# arduino.net
KiCad netlist of a schematic drawn in EAGLE
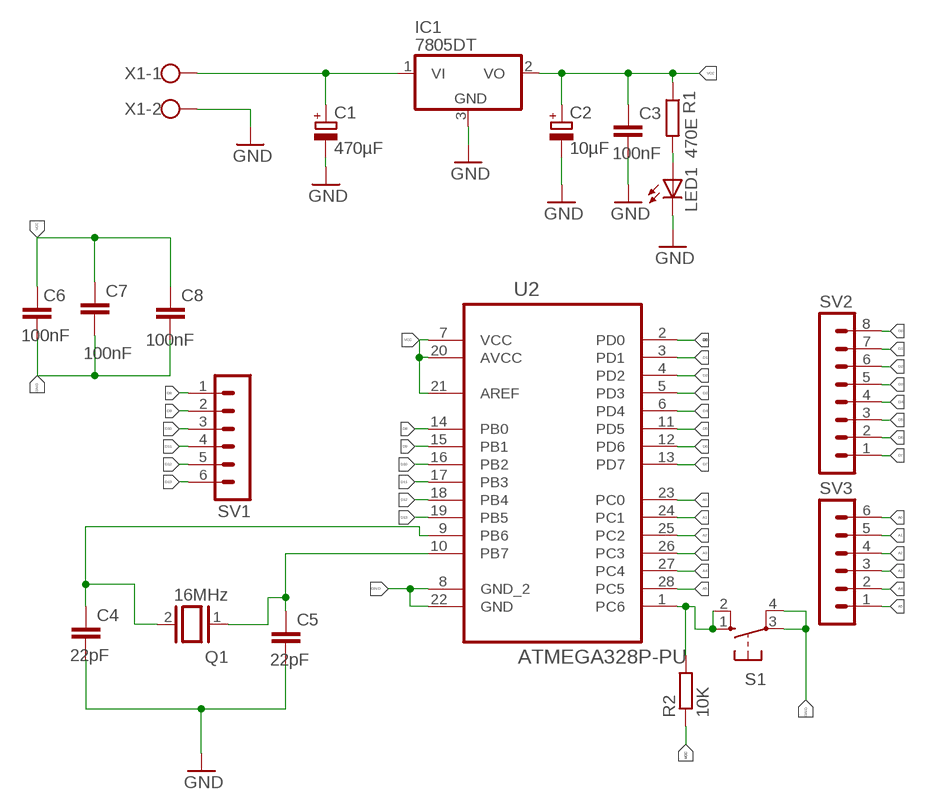
[diagram p0: schematic, sheet 1]

(export (version "E")
  (design (tool "Eeschema 10.0.6"))
  (components
    (comp (ref "C1")
      (value "470µF")
      (footprint "eagle-import:150CLZ-1010")
      (libsource (lib "eagle-import") (part "CPOL-EU150CLZ-1010"))
    )
    (comp (ref "C2")
      (value "10µF")
      (footprint "eagle-import:150CLZ-1010")
      (libsource (lib "eagle-import") (part "CPOL-EU150CLZ-1010"))
    )
    (comp (ref "C3")
      (value "100nF")
      (footprint "eagle-import:C1206")
      (libsource (lib "eagle-import") (part "C-EUC1206"))
    )
    (comp (ref "C4")
      (value "22pF")
      (footprint "eagle-import:C1206")
      (libsource (lib "eagle-import") (part "C-EUC1206"))
    )
    (comp (ref "C5")
      (value "22pF")
      (footprint "eagle-import:C1206")
      (libsource (lib "eagle-import") (part "C-EUC1206"))
    )
    (comp (ref "C6")
      (value "100nF")
      (footprint "eagle-import:C1206")
      (libsource (lib "eagle-import") (part "C-EUC1206"))
    )
    (comp (ref "C7")
      (value "100nF")
      (footprint "eagle-import:C1206")
      (libsource (lib "eagle-import") (part "C-EUC1206"))
    )
    (comp (ref "C8")
      (value "100nF")
      (footprint "eagle-import:C1206")
      (libsource (lib "eagle-import") (part "C-EUC1206"))
    )
    (comp (ref "IC1")
      (value "7805DT")
      (footprint "eagle-import:TO252")
      (libsource (lib "eagle-import") (part "78DT05"))
    )
    (comp (ref "LED1")
      (value "LEDSMT1206")
      (footprint "eagle-import:1206")
      (libsource (lib "eagle-import") (part "LEDSMT1206"))
    )
    (comp (ref "Q1")
      (value "16MHz")
      (footprint "eagle-import:QS")
      (libsource (lib "eagle-import") (part "XTAL/S"))
    )
    (comp (ref "R1")
      (value "470E")
      (footprint "eagle-import:M1206")
      (libsource (lib "eagle-import") (part "resistor_R-EU_M1206"))
    )
    (comp (ref "R2")
      (value "10K")
      (footprint "eagle-import:R1206")
      (libsource (lib "eagle-import") (part "R-EU_R1206"))
    )
    (comp (ref "S1")
      (value "10-XX")
      (footprint "eagle-import:B3F-10XX")
      (fields (field (name "MPN") "B3F-1000"))
      (libsource (lib "eagle-import") (part "10-XX"))
    )
    (comp (ref "SV1")
      (value "MA06-1")
      (footprint "eagle-import:MA06-1")
      (libsource (lib "eagle-import") (part "MA06-1"))
    )
    (comp (ref "SV2")
      (value "MA08-1")
      (footprint "eagle-import:MA08-1")
      (libsource (lib "eagle-import") (part "MA08-1"))
    )
    (comp (ref "SV3")
      (value "MA06-1")
      (footprint "eagle-import:MA06-1")
      (libsource (lib "eagle-import") (part "MA06-1"))
    )
    (comp (ref "U2")
      (value "ATMEGA328P-PU")
      (footprint "eagle-import:DIP254P762X457-28")
      (fields (field (name "MF") "Microchip"))
      (libsource (lib "eagle-import") (part "ATMEGA328P-PU"))
    )
    (comp (ref "X1")
      (value "W237-102")
      (footprint "eagle-import:W237-102")
      (fields (field (name "MPN") "237-102"))
      (libsource (lib "eagle-import") (part "W237-102"))
    )
  )
  (nets
    (net (code "1") (name "A0") (class "Default")
      (node (ref "SV3") (pin "6") (pinfunction "6_6") (pintype "passive"))
      (node (ref "U2") (pin "23") (pinfunction "PC0_23") (pintype "bidirectional"))
    )
    (net (code "2") (name "A1") (class "Default")
      (node (ref "SV3") (pin "5") (pinfunction "5_5") (pintype "passive"))
      (node (ref "U2") (pin "24") (pinfunction "PC1_24") (pintype "bidirectional"))
    )
    (net (code "3") (name "A2") (class "Default")
      (node (ref "SV3") (pin "4") (pinfunction "4_4") (pintype "passive"))
      (node (ref "U2") (pin "25") (pinfunction "PC2_25") (pintype "bidirectional"))
    )
    (net (code "4") (name "A3") (class "Default")
      (node (ref "SV3") (pin "3") (pinfunction "3_3") (pintype "passive"))
      (node (ref "U2") (pin "26") (pinfunction "PC3_26") (pintype "bidirectional"))
    )
    (net (code "5") (name "A4") (class "Default")
      (node (ref "SV3") (pin "2") (pinfunction "2_2") (pintype "passive"))
      (node (ref "U2") (pin "27") (pinfunction "PC4_27") (pintype "bidirectional"))
    )
    (net (code "6") (name "A5") (class "Default")
      (node (ref "SV3") (pin "1") (pinfunction "1_1") (pintype "passive"))
      (node (ref "U2") (pin "28") (pinfunction "PC5_28") (pintype "bidirectional"))
    )
    (net (code "7") (name "D0") (class "Default")
      (node (ref "SV2") (pin "8") (pinfunction "8_8") (pintype "passive"))
      (node (ref "U2") (pin "2") (pinfunction "PD0_2") (pintype "bidirectional"))
    )
    (net (code "8") (name "D1") (class "Default")
      (node (ref "SV2") (pin "7") (pinfunction "7_7") (pintype "passive"))
      (node (ref "U2") (pin "3") (pinfunction "PD1_3") (pintype "bidirectional"))
    )
    (net (code "9") (name "D2") (class "Default")
      (node (ref "SV2") (pin "6") (pinfunction "6_6") (pintype "passive"))
      (node (ref "U2") (pin "4") (pinfunction "PD2_4") (pintype "bidirectional"))
    )
    (net (code "10") (name "D3") (class "Default")
      (node (ref "SV2") (pin "5") (pinfunction "5_5") (pintype "passive"))
      (node (ref "U2") (pin "5") (pinfunction "PD3_5") (pintype "bidirectional"))
    )
    (net (code "11") (name "D4") (class "Default")
      (node (ref "SV2") (pin "4") (pinfunction "4_4") (pintype "passive"))
      (node (ref "U2") (pin "6") (pinfunction "PD4_6") (pintype "bidirectional"))
    )
    (net (code "12") (name "D5") (class "Default")
      (node (ref "SV2") (pin "3") (pinfunction "3_3") (pintype "passive"))
      (node (ref "U2") (pin "11") (pinfunction "PD5_11") (pintype "bidirectional"))
    )
    (net (code "13") (name "D6") (class "Default")
      (node (ref "SV2") (pin "2") (pinfunction "2_2") (pintype "passive"))
      (node (ref "U2") (pin "12") (pinfunction "PD6_12") (pintype "bidirectional"))
    )
    (net (code "14") (name "D7") (class "Default")
      (node (ref "SV2") (pin "1") (pinfunction "1_1") (pintype "passive"))
      (node (ref "U2") (pin "13") (pinfunction "PD7_13") (pintype "bidirectional"))
    )
    (net (code "15") (name "D8") (class "Default")
      (node (ref "SV1") (pin "1") (pinfunction "1_1") (pintype "passive"))
      (node (ref "U2") (pin "14") (pinfunction "PB0_14") (pintype "bidirectional"))
    )
    (net (code "16") (name "D9") (class "Default")
      (node (ref "SV1") (pin "2") (pinfunction "2_2") (pintype "passive"))
      (node (ref "U2") (pin "15") (pinfunction "PB1_15") (pintype "bidirectional"))
    )
    (net (code "17") (name "D10") (class "Default")
      (node (ref "SV1") (pin "3") (pinfunction "3_3") (pintype "passive"))
      (node (ref "U2") (pin "16") (pinfunction "PB2_16") (pintype "bidirectional"))
    )
    (net (code "18") (name "D11") (class "Default")
      (node (ref "SV1") (pin "4") (pinfunction "4_4") (pintype "passive"))
      (node (ref "U2") (pin "17") (pinfunction "PB3_17") (pintype "bidirectional"))
    )
    (net (code "19") (name "D12") (class "Default")
      (node (ref "SV1") (pin "5") (pinfunction "5_5") (pintype "passive"))
      (node (ref "U2") (pin "18") (pinfunction "PB4_18") (pintype "bidirectional"))
    )
    (net (code "20") (name "D13") (class "Default")
      (node (ref "SV1") (pin "6") (pinfunction "6_6") (pintype "passive"))
      (node (ref "U2") (pin "19") (pinfunction "PB5_19") (pintype "bidirectional"))
    )
    (net (code "21") (name "GND") (class "Default")
      (node (ref "C1") (pin "-") (pinfunction "-_-") (pintype "passive"))
      (node (ref "C2") (pin "-") (pinfunction "-_-") (pintype "passive"))
      (node (ref "C3") (pin "2") (pinfunction "2_2") (pintype "passive"))
      (node (ref "C4") (pin "2") (pinfunction "2_2") (pintype "passive"))
      (node (ref "C5") (pin "2") (pinfunction "2_2") (pintype "passive"))
      (node (ref "C6") (pin "2") (pinfunction "2_2") (pintype "passive"))
      (node (ref "C7") (pin "2") (pinfunction "2_2") (pintype "passive"))
      (node (ref "C8") (pin "2") (pinfunction "2_2") (pintype "passive"))
      (node (ref "IC1") (pin "3") (pinfunction "GND_3") (pintype "passive"))
      (node (ref "LED1") (pin "C") (pinfunction "C_C") (pintype "passive"))
      (node (ref "S1") (pin "3") (pinfunction "P_3") (pintype "passive"))
      (node (ref "S1") (pin "4") (pinfunction "P1_4") (pintype "passive"))
      (node (ref "U2") (pin "22") (pinfunction "GND_22") (pintype "passive"))
      (node (ref "U2") (pin "8") (pinfunction "GND_2_8") (pintype "passive"))
      (node (ref "X1") (pin "2") (pinfunction "KL_2") (pintype "passive"))
    )
    (net (code "22") (name "Net-(IC1-VI)") (class "Default")
      (node (ref "C1") (pin "+") (pinfunction "+_+") (pintype "passive"))
      (node (ref "IC1") (pin "1") (pinfunction "VI_1") (pintype "input"))
      (node (ref "X1") (pin "1") (pinfunction "KL_1") (pintype "passive"))
    )
    (net (code "23") (name "Net-(LED1-PadA)") (class "Default")
      (node (ref "LED1") (pin "A") (pinfunction "A_A") (pintype "passive"))
      (node (ref "R1") (pin "2") (pinfunction "2_2") (pintype "passive"))
    )
    (net (code "24") (name "Net-(S1-S)") (class "Default")
      (node (ref "R2") (pin "2") (pinfunction "2_2") (pintype "passive"))
      (node (ref "S1") (pin "1") (pinfunction "S_1") (pintype "passive"))
      (node (ref "S1") (pin "2") (pinfunction "S1_2") (pintype "passive"))
      (node (ref "U2") (pin "1") (pinfunction "PC6_1") (pintype "bidirectional"))
    )
    (net (code "25") (name "Net-(U2-PB6)") (class "Default")
      (node (ref "C4") (pin "1") (pinfunction "1_1") (pintype "passive"))
      (node (ref "Q1") (pin "2") (pinfunction "2_2") (pintype "passive"))
      (node (ref "U2") (pin "9") (pinfunction "PB6_9") (pintype "bidirectional"))
    )
    (net (code "26") (name "Net-(U2-PB7)") (class "Default")
      (node (ref "C5") (pin "1") (pinfunction "1_1") (pintype "passive"))
      (node (ref "Q1") (pin "1") (pinfunction "1_1") (pintype "passive"))
      (node (ref "U2") (pin "10") (pinfunction "PB7_10") (pintype "bidirectional"))
    )
    (net (code "27") (name "VCC") (class "Default")
      (node (ref "C2") (pin "+") (pinfunction "+_+") (pintype "passive"))
      (node (ref "C3") (pin "1") (pinfunction "1_1") (pintype "passive"))
      (node (ref "C6") (pin "1") (pinfunction "1_1") (pintype "passive"))
      (node (ref "C7") (pin "1") (pinfunction "1_1") (pintype "passive"))
      (node (ref "C8") (pin "1") (pinfunction "1_1") (pintype "passive"))
      (node (ref "IC1") (pin "2") (pinfunction "VO_2") (pintype "passive"))
      (node (ref "R1") (pin "1") (pinfunction "1_1") (pintype "passive"))
      (node (ref "R2") (pin "1") (pinfunction "1_1") (pintype "passive"))
      (node (ref "U2") (pin "20") (pinfunction "AVCC_20") (pintype "power_in"))
      (node (ref "U2") (pin "21") (pinfunction "AREF_21") (pintype "input"))
      (node (ref "U2") (pin "7") (pinfunction "VCC_7") (pintype "power_in"))
    )
  )
)
